# Stepper_driver_met_DVR8825_Pololu_compat.net
KiCad netlist of a schematic drawn in Altium Designer
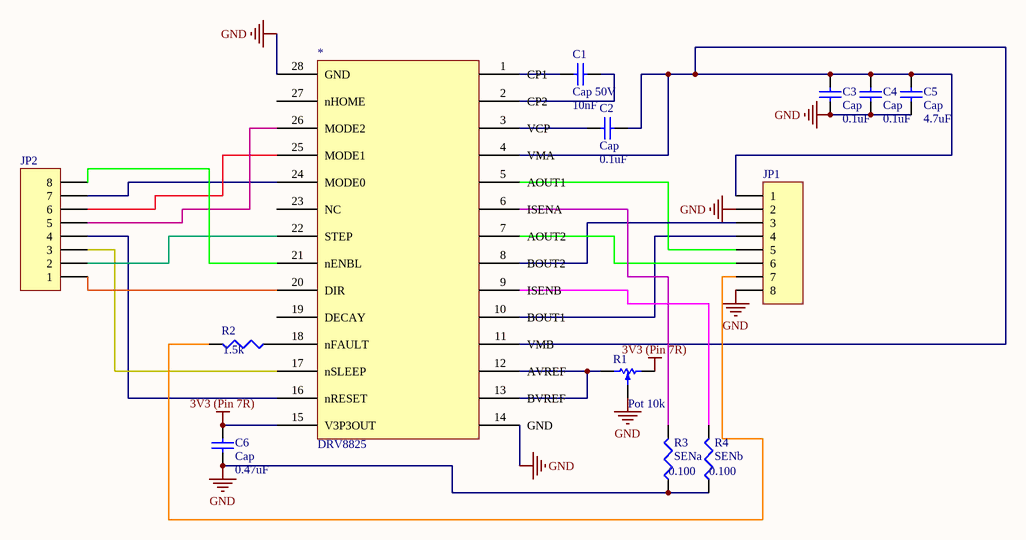
[diagram p0: Stepper driver met DVR8825 Pololu compatible.SchDoc]

(export (version "E")
  (design (tool "Eeschema 10.0.6"))
  (components
    (comp (ref "*") (value "DRV8825") (footprint "DRV8825") (libsource (lib "DRV8825") (part "DRV8825")))
    (comp (ref "C1")
      (value "Cap 50V")
      (footprint "CAPC1608M")
      (description "Capacitor (Semiconductor SIM Model)")
      (fields (field (name "ALTIUM_VALUE") "10nF") (field (name "PUBLISHER") "Altium Limited"))
      (libsource (lib "Miscellaneous Devices") (part "Cap Semi"))
    )
    (comp (ref "C2")
      (value "Cap")
      (footprint "CAPC1608M")
      (description "Capacitor (Semiconductor SIM Model)")
      (fields (field (name "ALTIUM_VALUE") "0.1uF") (field (name "PUBLISHER") "Altium Limited"))
      (libsource (lib "Miscellaneous Devices") (part "Cap Semi"))
    )
    (comp (ref "C3")
      (value "Cap")
      (footprint "CAPC1608M")
      (description "Capacitor (Semiconductor SIM Model)")
      (fields (field (name "ALTIUM_VALUE") "0.1uF") (field (name "PUBLISHER") "Altium Limited"))
      (libsource (lib "Miscellaneous Devices") (part "Cap Semi"))
    )
    (comp (ref "C4")
      (value "Cap")
      (footprint "CAPC1608M")
      (description "Capacitor (Semiconductor SIM Model)")
      (fields (field (name "ALTIUM_VALUE") "0.1uF") (field (name "PUBLISHER") "Altium Limited"))
      (libsource (lib "Miscellaneous Devices") (part "Cap Semi"))
    )
    (comp (ref "C5")
      (value "Cap")
      (footprint "C1210")
      (description "Capacitor (Semiconductor SIM Model)")
      (fields (field (name "ALTIUM_VALUE") "4.7uF") (field (name "PUBLISHER") "Altium Limited"))
      (libsource (lib "Miscellaneous Devices") (part "Cap Semi"))
    )
    (comp (ref "C6")
      (value "Cap")
      (footprint "CAPC1608M")
      (description "Capacitor (Semiconductor SIM Model)")
      (fields (field (name "ALTIUM_VALUE") "0.47uF") (field (name "PUBLISHER") "Altium Limited"))
      (libsource (lib "Miscellaneous Devices") (part "Cap Semi"))
    )
    (comp (ref "JP1")
      (value "eader 8")
      (footprint "HDR1X8 ZONDER OMLIJNING")
      (description "Header, 8-Pin")
      (fields (field (name "PUBLISHER") "Altium Limited"))
      (libsource (lib "") (part "Header 8_1"))
    )
    (comp (ref "JP2")
      (value "~")
      (footprint "HDR1X8 ZONDER OMLIJNING")
      (description "Header, 8-Pin")
      (fields (field (name "PUBLISHER") "Altium Limited"))
      (libsource (lib "Miscellaneous Connectors") (part "Header 8"))
    )
    (comp (ref "R1")
      (value "Pot 10k")
      (footprint "POT5MM")
      (description "Square Trimming Potentiometer")
      (fields (field (name "PUBLISHER") "Altium Limited"))
      (libsource (lib "Miscellaneous Devices") (part "RPot SM"))
    )
    (comp (ref "R2")
      (value "1.5k")
      (footprint "RESC1608M")
      (description "Resistor")
      (fields (field (name "PUBLISHER") "Altium Limited"))
      (libsource (lib "Miscellaneous Devices") (part "Res3"))
    )
    (comp (ref "R3")
      (value "SENa")
      (footprint "RESC2012M")
      (description "Resistor")
      (fields (field (name "ALTIUM_VALUE") "0.100") (field (name "PUBLISHER") "Altium Limited"))
      (libsource (lib "Miscellaneous Devices") (part "Res3"))
    )
    (comp (ref "R4")
      (value "SENb")
      (footprint "RESC2012M")
      (description "Resistor")
      (fields (field (name "ALTIUM_VALUE") "0.100") (field (name "PUBLISHER") "Altium Limited"))
      (libsource (lib "Miscellaneous Devices") (part "Res3"))
    )
  )
  (nets
    (net (code "1") (name "3V3 (Pin 7R)") (class "Default")
      (node (ref "*") (pin "15") (pinfunction "V3P3OUT_15") (pintype "passive"))
      (node (ref "C6") (pin "2") (pinfunction "2_2") (pintype "passive"))
      (node (ref "R1") (pin "CW") (pinfunction "+_CW") (pintype "passive"))
    )
    (net (code "2") (name "GND") (class "Default")
      (node (ref "*") (pin "28") (pinfunction "GND_28") (pintype "passive"))
      (node (ref "C3") (pin "1") (pinfunction "1_1") (pintype "passive"))
      (node (ref "C4") (pin "1") (pinfunction "1_1") (pintype "passive"))
      (node (ref "C5") (pin "1") (pinfunction "1_1") (pintype "passive"))
      (node (ref "C6") (pin "1") (pinfunction "1_1") (pintype "passive"))
      (node (ref "JP1") (pin "2") (pinfunction "2_2") (pintype "passive"))
      (node (ref "JP1") (pin "8") (pinfunction "8_8") (pintype "passive"))
      (node (ref "R1") (pin "W") (pinfunction "W_W") (pintype "passive"))
      (node (ref "R3") (pin "1") (pinfunction "1_1") (pintype "passive"))
      (node (ref "R4") (pin "1") (pinfunction "1_1") (pintype "passive"))
    )
    (net (code "3") (name "Net-(*-DIR)") (class "Default")
      (node (ref "*") (pin "20") (pinfunction "DIR_20") (pintype "passive"))
      (node (ref "JP2") (pin "1") (pinfunction "1_1") (pintype "passive"))
    )
    (net (code "4") (name "Net-(*-MODE0)") (class "Default")
      (node (ref "*") (pin "24") (pinfunction "MODE0_24") (pintype "passive"))
      (node (ref "JP2") (pin "7") (pinfunction "7_7") (pintype "passive"))
    )
    (net (code "5") (name "Net-(*-MODE1)") (class "Default")
      (node (ref "*") (pin "25") (pinfunction "MODE1_25") (pintype "passive"))
      (node (ref "JP2") (pin "6") (pinfunction "6_6") (pintype "passive"))
    )
    (net (code "6") (name "Net-(*-MODE2)") (class "Default")
      (node (ref "*") (pin "26") (pinfunction "MODE2_26") (pintype "passive"))
      (node (ref "JP2") (pin "5") (pinfunction "5_5") (pintype "passive"))
    )
    (net (code "7") (name "Net-(*-STEP)") (class "Default")
      (node (ref "*") (pin "22") (pinfunction "STEP_22") (pintype "passive"))
      (node (ref "JP2") (pin "2") (pinfunction "2_2") (pintype "passive"))
    )
    (net (code "8") (name "Net-(*-nENBL)") (class "Default")
      (node (ref "*") (pin "21") (pinfunction "nENBL_21") (pintype "passive"))
      (node (ref "JP2") (pin "8") (pinfunction "8_8") (pintype "passive"))
    )
    (net (code "9") (name "Net-(*-nFAULT)") (class "Default")
      (node (ref "*") (pin "18") (pinfunction "nFAULT_18") (pintype "passive"))
      (node (ref "R2") (pin "1") (pinfunction "1_1") (pintype "passive"))
    )
    (net (code "10") (name "Net-(*-nRESET)") (class "Default")
      (node (ref "*") (pin "16") (pinfunction "nRESET_16") (pintype "passive"))
      (node (ref "JP2") (pin "4") (pinfunction "4_4") (pintype "passive"))
    )
    (net (code "11") (name "Net-(*-nSLEEP)") (class "Default")
      (node (ref "*") (pin "17") (pinfunction "nSLEEP_17") (pintype "passive"))
      (node (ref "JP2") (pin "3") (pinfunction "3_3") (pintype "passive"))
    )
    (net (code "12") (name "Net-(C2-Pad1)") (class "Default")
      (node (ref "C2") (pin "1") (pinfunction "1_1") (pintype "passive"))
      (node (ref "C3") (pin "2") (pinfunction "2_2") (pintype "passive"))
      (node (ref "C4") (pin "2") (pinfunction "2_2") (pintype "passive"))
      (node (ref "C5") (pin "2") (pinfunction "2_2") (pintype "passive"))
      (node (ref "JP1") (pin "1") (pinfunction "1_1") (pintype "passive"))
    )
    (net (code "13") (name "Net-(JP1-Pad7)") (class "Default")
      (node (ref "JP1") (pin "7") (pinfunction "7_7") (pintype "passive"))
      (node (ref "R2") (pin "2") (pinfunction "2_2") (pintype "passive"))
    )
    (net (code "14") (name "unconnected-(*-AOUT1-Pad5)") (class "Default")
      (node (ref "*") (pin "5") (pinfunction "AOUT1_5") (pintype "passive"))
    )
    (net (code "15") (name "unconnected-(*-AOUT2-Pad7)") (class "Default")
      (node (ref "*") (pin "7") (pinfunction "AOUT2_7") (pintype "passive"))
    )
    (net (code "16") (name "unconnected-(*-AVREF-Pad12)") (class "Default")
      (node (ref "*") (pin "12") (pinfunction "AVREF_12") (pintype "passive"))
    )
    (net (code "17") (name "unconnected-(*-BOUT1-Pad10)") (class "Default")
      (node (ref "*") (pin "10") (pinfunction "BOUT1_10") (pintype "passive"))
    )
    (net (code "18") (name "unconnected-(*-BOUT2-Pad8)") (class "Default")
      (node (ref "*") (pin "8") (pinfunction "BOUT2_8") (pintype "passive"))
    )
    (net (code "19") (name "unconnected-(*-BVREF-Pad13)") (class "Default")
      (node (ref "*") (pin "13") (pinfunction "BVREF_13") (pintype "passive"))
    )
    (net (code "20") (name "unconnected-(*-CP1-Pad1)") (class "Default")
      (node (ref "*") (pin "1") (pinfunction "CP1_1") (pintype "passive"))
    )
    (net (code "21") (name "unconnected-(*-CP2-Pad2)") (class "Default")
      (node (ref "*") (pin "2") (pinfunction "CP2_2") (pintype "passive"))
    )
    (net (code "22") (name "unconnected-(*-DECAY-Pad19)") (class "Default")
      (node (ref "*") (pin "19") (pinfunction "DECAY_19") (pintype "passive"))
    )
    (net (code "23") (name "unconnected-(*-GND-Pad14)") (class "Default")
      (node (ref "*") (pin "14") (pinfunction "GND_14") (pintype "passive"))
    )
    (net (code "24") (name "unconnected-(*-ISENA-Pad6)") (class "Default")
      (node (ref "*") (pin "6") (pinfunction "ISENA_6") (pintype "passive"))
    )
    (net (code "25") (name "unconnected-(*-ISENB-Pad9)") (class "Default")
      (node (ref "*") (pin "9") (pinfunction "ISENB_9") (pintype "passive"))
    )
    (net (code "26") (name "unconnected-(*-NC-Pad23)") (class "Default")
      (node (ref "*") (pin "23") (pinfunction "NC_23") (pintype "passive"))
    )
    (net (code "27") (name "unconnected-(*-VCP-Pad3)") (class "Default")
      (node (ref "*") (pin "3") (pinfunction "VCP_3") (pintype "passive"))
    )
    (net (code "28") (name "unconnected-(*-VMA-Pad4)") (class "Default")
      (node (ref "*") (pin "4") (pinfunction "VMA_4") (pintype "passive"))
    )
    (net (code "29") (name "unconnected-(*-VMB-Pad11)") (class "Default")
      (node (ref "*") (pin "11") (pinfunction "VMB_11") (pintype "passive"))
    )
    (net (code "30") (name "unconnected-(*-nHOME-Pad27)") (class "Default")
      (node (ref "*") (pin "27") (pinfunction "nHOME_27") (pintype "passive"))
    )
    (net (code "31") (name "unconnected-(C1-Pad1)") (class "Default")
      (node (ref "C1") (pin "1") (pinfunction "1_1") (pintype "passive"))
    )
    (net (code "32") (name "unconnected-(C1-Pad2)") (class "Default")
      (node (ref "C1") (pin "2") (pinfunction "2_2") (pintype "passive"))
    )
    (net (code "33") (name "unconnected-(C2-Pad2)") (class "Default")
      (node (ref "C2") (pin "2") (pinfunction "2_2") (pintype "passive"))
    )
    (net (code "34") (name "unconnected-(JP1-Pad3)") (class "Default")
      (node (ref "JP1") (pin "3") (pinfunction "3_3") (pintype "passive"))
    )
    (net (code "35") (name "unconnected-(JP1-Pad4)") (class "Default")
      (node (ref "JP1") (pin "4") (pinfunction "4_4") (pintype "passive"))
    )
    (net (code "36") (name "unconnected-(JP1-Pad5)") (class "Default")
      (node (ref "JP1") (pin "5") (pinfunction "5_5") (pintype "passive"))
    )
    (net (code "37") (name "unconnected-(JP1-Pad6)") (class "Default")
      (node (ref "JP1") (pin "6") (pinfunction "6_6") (pintype "passive"))
    )
    (net (code "38") (name "unconnected-(R1---PadCCW)") (class "Default")
      (node (ref "R1") (pin "CCW") (pinfunction "-_CCW") (pintype "passive"))
    )
    (net (code "39") (name "unconnected-(R3-Pad2)") (class "Default")
      (node (ref "R3") (pin "2") (pinfunction "2_2") (pintype "passive"))
    )
    (net (code "40") (name "unconnected-(R4-Pad2)") (class "Default")
      (node (ref "R4") (pin "2") (pinfunction "2_2") (pintype "passive"))
    )
  )
)
